# breakout.net
KiCad netlist of a schematic drawn in EAGLE
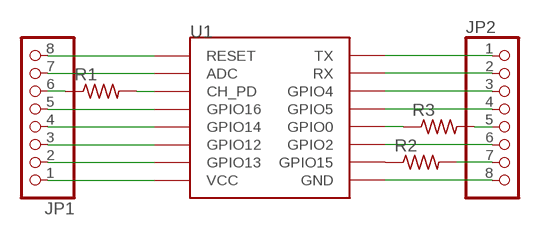
[diagram p0: schematic, sheet 1]

(export (version "E")
  (design (tool "Eeschema 10.0.6"))
  (components
    (comp (ref "JP1")
      (value "PINHD-1X8_2.54")
      (footprint "eagle-import:1X08")
      (libsource (lib "eagle-import") (part "PINHD-1X8_2.54"))
    )
    (comp (ref "JP2")
      (value "PINHD-1X8_2.54")
      (footprint "eagle-import:1X08")
      (libsource (lib "eagle-import") (part "PINHD-1X8_2.54"))
    )
    (comp (ref "R1")
      (value "R-US_R0805")
      (footprint "eagle-import:R0805")
      (libsource (lib "eagle-import") (part "R-US_R0805"))
    )
    (comp (ref "R2")
      (value "R-US_R0805")
      (footprint "eagle-import:R0805")
      (libsource (lib "eagle-import") (part "R-US_R0805"))
    )
    (comp (ref "R3")
      (value "R-US_R0805")
      (footprint "eagle-import:R0805")
      (libsource (lib "eagle-import") (part "R-US_R0805"))
    )
    (comp (ref "U1")
      (value "ESP12SMD")
      (footprint "eagle-import:ESP12-SMD")
      (libsource (lib "eagle-import") (part "ESP12SMD"))
    )
  )
  (nets
    (net (code "1") (name "Net-(JP1-Pad1)") (class "Default")
      (node (ref "JP1") (pin "1") (pinfunction "1_1") (pintype "passive"))
      (node (ref "U1") (pin "VCC") (pinfunction "VCC_VCC") (pintype "bidirectional"))
    )
    (net (code "2") (name "Net-(JP1-Pad2)") (class "Default")
      (node (ref "JP1") (pin "2") (pinfunction "2_2") (pintype "passive"))
      (node (ref "U1") (pin "GPIO13") (pinfunction "GPIO13_GPIO13") (pintype "bidirectional"))
    )
    (net (code "3") (name "Net-(JP1-Pad3)") (class "Default")
      (node (ref "JP1") (pin "3") (pinfunction "3_3") (pintype "passive"))
      (node (ref "U1") (pin "GPIO12") (pinfunction "GPIO12_GPIO12") (pintype "bidirectional"))
    )
    (net (code "4") (name "Net-(JP1-Pad4)") (class "Default")
      (node (ref "JP1") (pin "4") (pinfunction "4_4") (pintype "passive"))
      (node (ref "U1") (pin "GPIO14") (pinfunction "GPIO14_GPIO14") (pintype "bidirectional"))
    )
    (net (code "5") (name "Net-(JP1-Pad5)") (class "Default")
      (node (ref "JP1") (pin "5") (pinfunction "5_5") (pintype "passive"))
      (node (ref "U1") (pin "GPIO16") (pinfunction "GPIO16_GPIO16") (pintype "bidirectional"))
    )
    (net (code "6") (name "Net-(JP1-Pad6)") (class "Default")
      (node (ref "JP1") (pin "6") (pinfunction "6_6") (pintype "passive"))
      (node (ref "R1") (pin "1") (pinfunction "1_1") (pintype "passive"))
    )
    (net (code "7") (name "Net-(JP1-Pad7)") (class "Default")
      (node (ref "JP1") (pin "7") (pinfunction "7_7") (pintype "passive"))
      (node (ref "U1") (pin "ADC") (pinfunction "ADC_ADC") (pintype "bidirectional"))
    )
    (net (code "8") (name "Net-(JP1-Pad8)") (class "Default")
      (node (ref "JP1") (pin "8") (pinfunction "8_8") (pintype "passive"))
      (node (ref "U1") (pin "RESET") (pinfunction "RESET_RESET") (pintype "bidirectional"))
    )
    (net (code "9") (name "Net-(JP2-Pad3)") (class "Default")
      (node (ref "JP2") (pin "3") (pinfunction "3_3") (pintype "passive"))
      (node (ref "U1") (pin "GPIO4") (pinfunction "GPIO4_GPIO4") (pintype "bidirectional"))
    )
    (net (code "10") (name "Net-(JP2-Pad4)") (class "Default")
      (node (ref "JP2") (pin "4") (pinfunction "4_4") (pintype "passive"))
      (node (ref "U1") (pin "GPIO5") (pinfunction "GPIO5_GPIO5") (pintype "bidirectional"))
    )
    (net (code "11") (name "Net-(JP2-Pad5)") (class "Default")
      (node (ref "JP2") (pin "5") (pinfunction "5_5") (pintype "passive"))
      (node (ref "R3") (pin "2") (pinfunction "2_2") (pintype "passive"))
    )
    (net (code "12") (name "Net-(JP2-Pad6)") (class "Default")
      (node (ref "JP2") (pin "6") (pinfunction "6_6") (pintype "passive"))
      (node (ref "U1") (pin "GPIO2") (pinfunction "GPIO2_GPIO2") (pintype "bidirectional"))
    )
    (net (code "13") (name "Net-(JP2-Pad7)") (class "Default")
      (node (ref "JP2") (pin "7") (pinfunction "7_7") (pintype "passive"))
      (node (ref "R2") (pin "2") (pinfunction "2_2") (pintype "passive"))
    )
    (net (code "14") (name "Net-(JP2-Pad8)") (class "Default")
      (node (ref "JP2") (pin "8") (pinfunction "8_8") (pintype "passive"))
      (node (ref "U1") (pin "GND") (pinfunction "GND_GND") (pintype "bidirectional"))
    )
    (net (code "15") (name "Net-(R1-Pad2)") (class "Default")
      (node (ref "R1") (pin "2") (pinfunction "2_2") (pintype "passive"))
      (node (ref "U1") (pin "CH_PD") (pinfunction "CH_PD_CH_PD") (pintype "bidirectional"))
    )
    (net (code "16") (name "Net-(R2-Pad1)") (class "Default")
      (node (ref "R2") (pin "1") (pinfunction "1_1") (pintype "passive"))
      (node (ref "U1") (pin "GPIO15") (pinfunction "GPIO15_GPIO15") (pintype "bidirectional"))
    )
    (net (code "17") (name "Net-(R3-Pad1)") (class "Default")
      (node (ref "R3") (pin "1") (pinfunction "1_1") (pintype "passive"))
      (node (ref "U1") (pin "GPIO0") (pinfunction "GPIO0_GPIO0") (pintype "bidirectional"))
    )
    (net (code "18") (name "Net-(U1-RX)") (class "Default")
      (node (ref "JP2") (pin "2") (pinfunction "2_2") (pintype "passive"))
      (node (ref "U1") (pin "RXD0") (pinfunction "RX_RXD0") (pintype "bidirectional"))
    )
    (net (code "19") (name "Net-(U1-TX)") (class "Default")
      (node (ref "JP2") (pin "1") (pinfunction "1_1") (pintype "passive"))
      (node (ref "U1") (pin "TXD0") (pinfunction "TX_TXD0") (pintype "bidirectional"))
    )
  )
)
